# 05_USB_HUB.net
KiCad netlist of a schematic drawn in Altium Designer
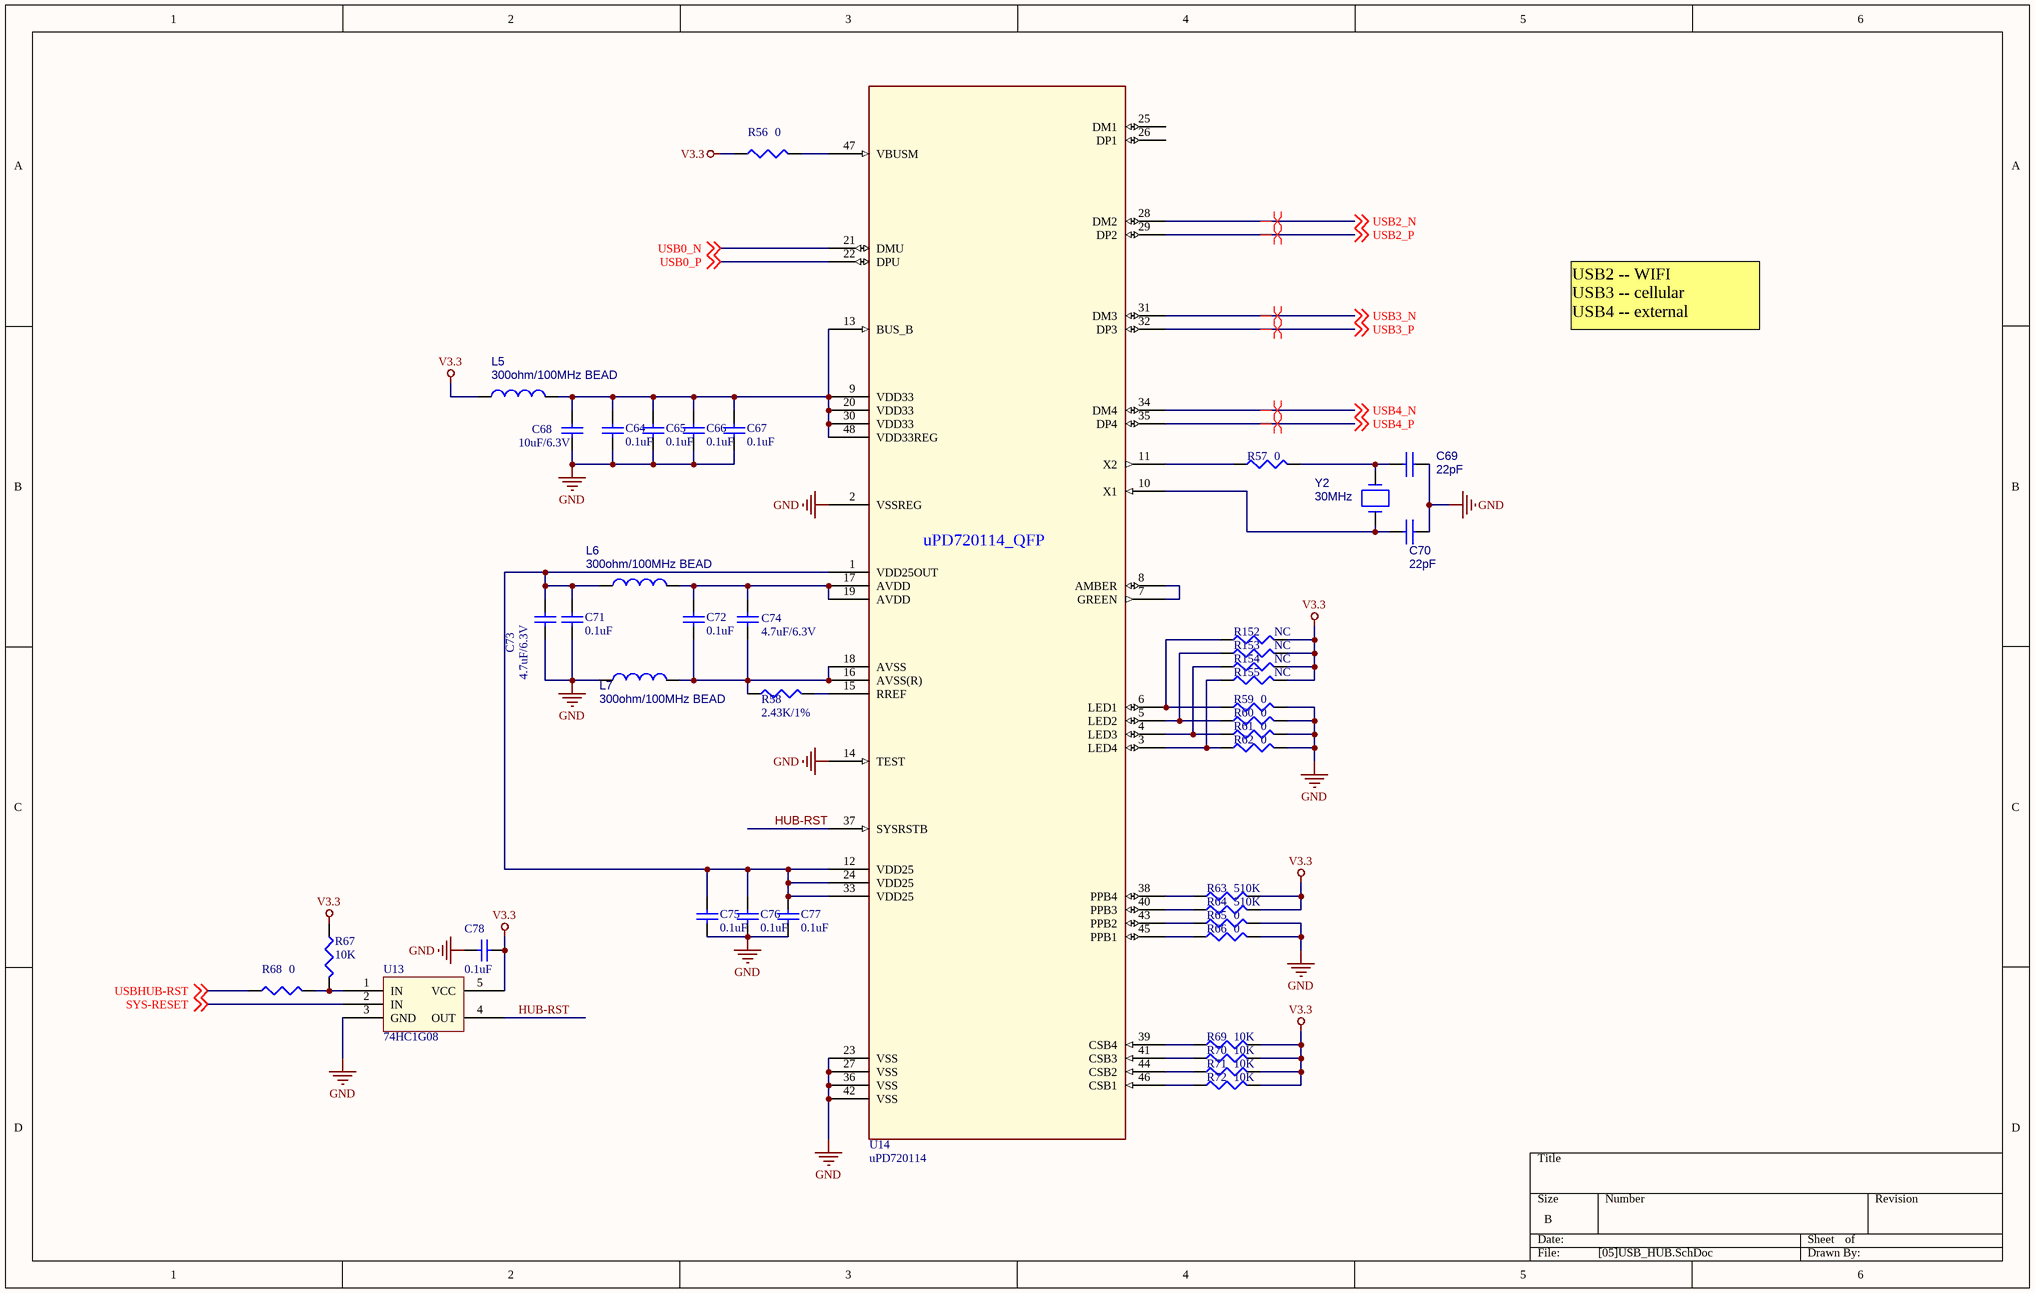
[diagram p0: [05]USB_HUB.SchDoc]

(export (version "E")
  (design (tool "Eeschema 10.0.6"))
  (components
    (comp (ref "C64")
      (value "0.1uF")
      (footprint "0603")
      (description "Capacitor")
      (libsource (lib "Miscellaneous Devices") (part "Cap"))
    )
    (comp (ref "C65")
      (value "0.1uF")
      (footprint "0603")
      (description "Capacitor")
      (libsource (lib "Miscellaneous Devices") (part "Cap"))
    )
    (comp (ref "C66")
      (value "0.1uF")
      (footprint "0603")
      (description "Capacitor")
      (libsource (lib "Miscellaneous Devices") (part "Cap"))
    )
    (comp (ref "C67")
      (value "0.1uF")
      (footprint "0603")
      (description "Capacitor")
      (libsource (lib "Miscellaneous Devices") (part "Cap"))
    )
    (comp (ref "C68")
      (value "10uF/6.3V")
      (footprint "0805")
      (description "Capacitor")
      (libsource (lib "Miscellaneous Devices") (part "Cap"))
    )
    (comp (ref "C69") (value "22pF") (libsource (lib "*") (part "CAP_Dup1")))
    (comp (ref "C70") (value "22pF") (libsource (lib "*") (part "CAP_Dup1")))
    (comp (ref "C71")
      (value "0.1uF")
      (footprint "0603")
      (description "Capacitor")
      (libsource (lib "Miscellaneous Devices") (part "Cap"))
    )
    (comp (ref "C72")
      (value "0.1uF")
      (footprint "0603")
      (description "Capacitor")
      (libsource (lib "Miscellaneous Devices") (part "Cap"))
    )
    (comp (ref "C73")
      (value "4.7uF/6.3V")
      (footprint "0603")
      (description "Capacitor")
      (libsource (lib "Miscellaneous Devices") (part "Cap"))
    )
    (comp (ref "C74")
      (value "4.7uF/6.3V")
      (footprint "0603")
      (description "Capacitor")
      (libsource (lib "Miscellaneous Devices") (part "Cap"))
    )
    (comp (ref "C75")
      (value "0.1uF")
      (footprint "0603")
      (description "Capacitor")
      (libsource (lib "Miscellaneous Devices") (part "Cap"))
    )
    (comp (ref "C76")
      (value "0.1uF")
      (footprint "0603")
      (description "Capacitor")
      (libsource (lib "Miscellaneous Devices") (part "Cap"))
    )
    (comp (ref "C77")
      (value "0.1uF")
      (footprint "0603")
      (description "Capacitor")
      (libsource (lib "Miscellaneous Devices") (part "Cap"))
    )
    (comp (ref "C78")
      (value "0.1uF")
      (footprint "0603")
      (description "Capacitor")
      (libsource (lib "Miscellaneous Devices") (part "Cap"))
    )
    (comp (ref "L5") (value "300ohm/100MHz BEAD") (libsource (lib "*") (part "INDUCTOR_4")))
    (comp (ref "L6") (value "300ohm/100MHz BEAD") (libsource (lib "*") (part "INDUCTOR_4")))
    (comp (ref "L7") (value "300ohm/100MHz BEAD") (libsource (lib "*") (part "INDUCTOR_4")))
    (comp (ref "R56")
      (value "0")
      (footprint "0603")
      (description "Resistor")
      (libsource (lib "Miscellaneous Devices") (part "Res3"))
    )
    (comp (ref "R57")
      (value "0")
      (footprint "0603")
      (description "Resistor")
      (libsource (lib "Miscellaneous Devices") (part "Res3"))
    )
    (comp (ref "R58")
      (value "2.43K/1%")
      (footprint "0603")
      (description "Resistor")
      (libsource (lib "Miscellaneous Devices") (part "Res3"))
    )
    (comp (ref "R59")
      (value "0")
      (footprint "0603")
      (description "Resistor")
      (libsource (lib "Miscellaneous Devices") (part "Res3"))
    )
    (comp (ref "R60")
      (value "0")
      (footprint "0603")
      (description "Resistor")
      (libsource (lib "Miscellaneous Devices") (part "Res3"))
    )
    (comp (ref "R61")
      (value "0")
      (footprint "0603")
      (description "Resistor")
      (libsource (lib "Miscellaneous Devices") (part "Res3"))
    )
    (comp (ref "R62")
      (value "0")
      (footprint "0603")
      (description "Resistor")
      (libsource (lib "Miscellaneous Devices") (part "Res3"))
    )
    (comp (ref "R63")
      (value "510K")
      (footprint "0603")
      (description "Resistor")
      (libsource (lib "Miscellaneous Devices") (part "Res3"))
    )
    (comp (ref "R64")
      (value "510K")
      (footprint "0603")
      (description "Resistor")
      (libsource (lib "Miscellaneous Devices") (part "Res3"))
    )
    (comp (ref "R65")
      (value "0")
      (footprint "0603")
      (description "Resistor")
      (libsource (lib "Miscellaneous Devices") (part "Res3"))
    )
    (comp (ref "R66")
      (value "0")
      (footprint "0603")
      (description "Resistor")
      (libsource (lib "Miscellaneous Devices") (part "Res3"))
    )
    (comp (ref "R67")
      (value "10K")
      (footprint "0603")
      (description "Resistor")
      (libsource (lib "Miscellaneous Devices") (part "Res3"))
    )
    (comp (ref "R68")
      (value "0")
      (footprint "0603")
      (description "Resistor")
      (libsource (lib "Miscellaneous Devices") (part "Res3"))
    )
    (comp (ref "R69")
      (value "10K")
      (footprint "0603")
      (description "Resistor")
      (libsource (lib "Miscellaneous Devices") (part "Res3"))
    )
    (comp (ref "R70")
      (value "10K")
      (footprint "0603")
      (description "Resistor")
      (libsource (lib "Miscellaneous Devices") (part "Res3"))
    )
    (comp (ref "R71")
      (value "10K")
      (footprint "0603")
      (description "Resistor")
      (libsource (lib "Miscellaneous Devices") (part "Res3"))
    )
    (comp (ref "R72")
      (value "10K")
      (footprint "0603")
      (description "Resistor")
      (libsource (lib "Miscellaneous Devices") (part "Res3"))
    )
    (comp (ref "R152")
      (value "NC")
      (footprint "0603")
      (description "Resistor")
      (libsource (lib "Miscellaneous Devices") (part "Res3"))
    )
    (comp (ref "R153")
      (value "NC")
      (footprint "0603")
      (description "Resistor")
      (libsource (lib "Miscellaneous Devices") (part "Res3"))
    )
    (comp (ref "R154")
      (value "NC")
      (footprint "0603")
      (description "Resistor")
      (libsource (lib "Miscellaneous Devices") (part "Res3"))
    )
    (comp (ref "R155")
      (value "NC")
      (footprint "0603")
      (description "Resistor")
      (libsource (lib "Miscellaneous Devices") (part "Res3"))
    )
    (comp (ref "U13") (value "74HC1G08") (footprint "SOT23-5") (libsource (lib "Schlib") (part "74HC1G08")))
    (comp (ref "U14") (value "uPD720114") (footprint "LQFP48") (libsource (lib "*") (part "upd720114_QFP_4")))
    (comp (ref "Y2") (value "30MHz") (libsource (lib "*") (part "CRYSTAL")))
  )
  (nets
    (net (code "1") (name "/HUB-RST") (class "Default")
      (node (ref "U13") (pin "4") (pinfunction "OUT_4") (pintype "passive"))
      (node (ref "U14") (pin "37") (pinfunction "SYSRSTB_37") (pintype "input"))
    )
    (net (code "2") (name "GND") (class "Default")
      (node (ref "C64") (pin "1") (pinfunction "1_1") (pintype "passive"))
      (node (ref "C65") (pin "1") (pinfunction "1_1") (pintype "passive"))
      (node (ref "C66") (pin "1") (pinfunction "1_1") (pintype "passive"))
      (node (ref "C67") (pin "1") (pinfunction "1_1") (pintype "passive"))
      (node (ref "C68") (pin "1") (pinfunction "1_1") (pintype "passive"))
      (node (ref "C69") (pin "1") (pinfunction "1_1") (pintype "passive"))
      (node (ref "C70") (pin "1") (pinfunction "1_1") (pintype "passive"))
      (node (ref "C71") (pin "1") (pinfunction "1_1") (pintype "passive"))
      (node (ref "C73") (pin "1") (pinfunction "1_1") (pintype "passive"))
      (node (ref "C75") (pin "1") (pinfunction "1_1") (pintype "passive"))
      (node (ref "C76") (pin "1") (pinfunction "1_1") (pintype "passive"))
      (node (ref "C77") (pin "1") (pinfunction "1_1") (pintype "passive"))
      (node (ref "C78") (pin "2") (pinfunction "2_2") (pintype "passive"))
      (node (ref "L7") (pin "2") (pinfunction "2_2") (pintype "passive"))
      (node (ref "R59") (pin "2") (pinfunction "2_2") (pintype "passive"))
      (node (ref "R60") (pin "2") (pinfunction "2_2") (pintype "passive"))
      (node (ref "R61") (pin "2") (pinfunction "2_2") (pintype "passive"))
      (node (ref "R62") (pin "2") (pinfunction "2_2") (pintype "passive"))
      (node (ref "R65") (pin "2") (pinfunction "2_2") (pintype "passive"))
      (node (ref "R66") (pin "2") (pinfunction "2_2") (pintype "passive"))
      (node (ref "U13") (pin "3") (pinfunction "GND_3") (pintype "passive"))
      (node (ref "U14") (pin "14") (pinfunction "TEST_14") (pintype "input"))
      (node (ref "U14") (pin "2") (pinfunction "VSSREG_2") (pintype "power_in"))
      (node (ref "U14") (pin "23") (pinfunction "VSS_23") (pintype "power_in"))
      (node (ref "U14") (pin "27") (pinfunction "VSS_27") (pintype "power_in"))
      (node (ref "U14") (pin "36") (pinfunction "VSS_36") (pintype "power_in"))
      (node (ref "U14") (pin "42") (pinfunction "VSS_42") (pintype "power_in"))
    )
    (net (code "3") (name "Net-(C69-Pad2)") (class "Default")
      (node (ref "C69") (pin "2") (pinfunction "2_2") (pintype "passive"))
      (node (ref "R57") (pin "2") (pinfunction "2_2") (pintype "passive"))
      (node (ref "Y2") (pin "2") (pinfunction "2_2") (pintype "passive"))
    )
    (net (code "4") (name "Net-(C72-Pad2)") (class "Default")
      (node (ref "C72") (pin "2") (pinfunction "2_2") (pintype "passive"))
      (node (ref "C74") (pin "2") (pinfunction "2_2") (pintype "passive"))
      (node (ref "L6") (pin "1") (pinfunction "1_1") (pintype "passive"))
      (node (ref "U14") (pin "17") (pinfunction "AVDD_17") (pintype "power_in"))
      (node (ref "U14") (pin "19") (pinfunction "AVDD_19") (pintype "power_in"))
    )
    (net (code "5") (name "Net-(R67-Pad2)") (class "Default")
      (node (ref "R67") (pin "2") (pinfunction "2_2") (pintype "passive"))
      (node (ref "R68") (pin "2") (pinfunction "2_2") (pintype "passive"))
      (node (ref "U13") (pin "1") (pinfunction "IN_1") (pintype "passive"))
    )
    (net (code "6") (name "Net-(U14-AMBER)") (class "Default")
      (node (ref "U14") (pin "7") (pinfunction "GREEN_7") (pintype "output"))
      (node (ref "U14") (pin "8") (pinfunction "AMBER_8") (pintype "bidirectional"))
    )
    (net (code "7") (name "Net-(U14-AVSS(R))") (class "Default")
      (node (ref "C72") (pin "1") (pinfunction "1_1") (pintype "passive"))
      (node (ref "C74") (pin "1") (pinfunction "1_1") (pintype "passive"))
      (node (ref "L7") (pin "1") (pinfunction "1_1") (pintype "passive"))
      (node (ref "R58") (pin "1") (pinfunction "1_1") (pintype "passive"))
      (node (ref "U14") (pin "16") (pinfunction "AVSS(R)_16") (pintype "power_in"))
      (node (ref "U14") (pin "18") (pinfunction "AVSS_18") (pintype "power_in"))
    )
    (net (code "8") (name "Net-(U14-BUS_B)") (class "Default")
      (node (ref "C64") (pin "2") (pinfunction "2_2") (pintype "passive"))
      (node (ref "C65") (pin "2") (pinfunction "2_2") (pintype "passive"))
      (node (ref "C66") (pin "2") (pinfunction "2_2") (pintype "passive"))
      (node (ref "C67") (pin "2") (pinfunction "2_2") (pintype "passive"))
      (node (ref "C68") (pin "2") (pinfunction "2_2") (pintype "passive"))
      (node (ref "L5") (pin "1") (pinfunction "1_1") (pintype "passive"))
      (node (ref "U14") (pin "13") (pinfunction "BUS_B_13") (pintype "input"))
      (node (ref "U14") (pin "20") (pinfunction "VDD33_20") (pintype "power_in"))
      (node (ref "U14") (pin "30") (pinfunction "VDD33_30") (pintype "power_in"))
      (node (ref "U14") (pin "48") (pinfunction "VDD33REG_48") (pintype "power_in"))
      (node (ref "U14") (pin "9") (pinfunction "VDD33_9") (pintype "power_in"))
    )
    (net (code "9") (name "Net-(U14-CSB1)") (class "Default")
      (node (ref "R72") (pin "1") (pinfunction "1_1") (pintype "passive"))
      (node (ref "U14") (pin "46") (pinfunction "CSB1_46") (pintype "input"))
    )
    (net (code "10") (name "Net-(U14-CSB2)") (class "Default")
      (node (ref "R71") (pin "1") (pinfunction "1_1") (pintype "passive"))
      (node (ref "U14") (pin "44") (pinfunction "CSB2_44") (pintype "input"))
    )
    (net (code "11") (name "Net-(U14-CSB3)") (class "Default")
      (node (ref "R70") (pin "1") (pinfunction "1_1") (pintype "passive"))
      (node (ref "U14") (pin "41") (pinfunction "CSB3_41") (pintype "input"))
    )
    (net (code "12") (name "Net-(U14-CSB4)") (class "Default")
      (node (ref "R69") (pin "1") (pinfunction "1_1") (pintype "passive"))
      (node (ref "U14") (pin "39") (pinfunction "CSB4_39") (pintype "input"))
    )
    (net (code "13") (name "Net-(U14-LED1)") (class "Default")
      (node (ref "R152") (pin "1") (pinfunction "1_1") (pintype "passive"))
      (node (ref "R59") (pin "1") (pinfunction "1_1") (pintype "passive"))
      (node (ref "U14") (pin "6") (pinfunction "LED1_6") (pintype "bidirectional"))
    )
    (net (code "14") (name "Net-(U14-LED2)") (class "Default")
      (node (ref "R153") (pin "1") (pinfunction "1_1") (pintype "passive"))
      (node (ref "R60") (pin "1") (pinfunction "1_1") (pintype "passive"))
      (node (ref "U14") (pin "5") (pinfunction "LED2_5") (pintype "bidirectional"))
    )
    (net (code "15") (name "Net-(U14-LED3)") (class "Default")
      (node (ref "R154") (pin "1") (pinfunction "1_1") (pintype "passive"))
      (node (ref "R61") (pin "1") (pinfunction "1_1") (pintype "passive"))
      (node (ref "U14") (pin "4") (pinfunction "LED3_4") (pintype "bidirectional"))
    )
    (net (code "16") (name "Net-(U14-LED4)") (class "Default")
      (node (ref "R155") (pin "1") (pinfunction "1_1") (pintype "passive"))
      (node (ref "R62") (pin "1") (pinfunction "1_1") (pintype "passive"))
      (node (ref "U14") (pin "3") (pinfunction "LED4_3") (pintype "bidirectional"))
    )
    (net (code "17") (name "Net-(U14-PPB1)") (class "Default")
      (node (ref "R66") (pin "1") (pinfunction "1_1") (pintype "passive"))
      (node (ref "U14") (pin "45") (pinfunction "PPB1_45") (pintype "bidirectional"))
    )
    (net (code "18") (name "Net-(U14-PPB2)") (class "Default")
      (node (ref "R65") (pin "1") (pinfunction "1_1") (pintype "passive"))
      (node (ref "U14") (pin "43") (pinfunction "PPB2_43") (pintype "bidirectional"))
    )
    (net (code "19") (name "Net-(U14-PPB3)") (class "Default")
      (node (ref "R64") (pin "1") (pinfunction "1_1") (pintype "passive"))
      (node (ref "U14") (pin "40") (pinfunction "PPB3_40") (pintype "bidirectional"))
    )
    (net (code "20") (name "Net-(U14-PPB4)") (class "Default")
      (node (ref "R63") (pin "1") (pinfunction "1_1") (pintype "passive"))
      (node (ref "U14") (pin "38") (pinfunction "PPB4_38") (pintype "bidirectional"))
    )
    (net (code "21") (name "Net-(U14-RREF)") (class "Default")
      (node (ref "R58") (pin "2") (pinfunction "2_2") (pintype "passive"))
      (node (ref "U14") (pin "15") (pinfunction "RREF_15") (pintype "passive"))
    )
    (net (code "22") (name "Net-(U14-VBUSM)") (class "Default")
      (node (ref "R56") (pin "2") (pinfunction "2_2") (pintype "passive"))
      (node (ref "U14") (pin "47") (pinfunction "VBUSM_47") (pintype "input"))
    )
    (net (code "23") (name "Net-(U14-VDD25OUT)") (class "Default")
      (node (ref "C71") (pin "2") (pinfunction "2_2") (pintype "passive"))
      (node (ref "C73") (pin "2") (pinfunction "2_2") (pintype "passive"))
      (node (ref "C75") (pin "2") (pinfunction "2_2") (pintype "passive"))
      (node (ref "C76") (pin "2") (pinfunction "2_2") (pintype "passive"))
      (node (ref "C77") (pin "2") (pinfunction "2_2") (pintype "passive"))
      (node (ref "L6") (pin "2") (pinfunction "2_2") (pintype "passive"))
      (node (ref "U14") (pin "1") (pinfunction "VDD25OUT_1") (pintype "power_in"))
      (node (ref "U14") (pin "12") (pinfunction "VDD25_12") (pintype "power_in"))
      (node (ref "U14") (pin "24") (pinfunction "VDD25_24") (pintype "power_in"))
      (node (ref "U14") (pin "33") (pinfunction "VDD25_33") (pintype "power_in"))
    )
    (net (code "24") (name "Net-(U14-X1)") (class "Default")
      (node (ref "C70") (pin "2") (pinfunction "2_2") (pintype "passive"))
      (node (ref "U14") (pin "10") (pinfunction "X1_10") (pintype "input"))
      (node (ref "Y2") (pin "1") (pinfunction "1_1") (pintype "passive"))
    )
    (net (code "25") (name "Net-(U14-X2)") (class "Default")
      (node (ref "R57") (pin "1") (pinfunction "1_1") (pintype "passive"))
      (node (ref "U14") (pin "11") (pinfunction "X2_11") (pintype "output"))
    )
    (net (code "26") (name "SYS-RESET") (class "Default")
      (node (ref "U13") (pin "2") (pinfunction "IN_2") (pintype "passive"))
    )
    (net (code "27") (name "USB0_N") (class "Default")
      (node (ref "U14") (pin "21") (pinfunction "DMU_21") (pintype "bidirectional"))
    )
    (net (code "28") (name "USB0_P") (class "Default")
      (node (ref "U14") (pin "22") (pinfunction "DPU_22") (pintype "bidirectional"))
    )
    (net (code "29") (name "USB2_N") (class "Default")
      (node (ref "U14") (pin "28") (pinfunction "DM2_28") (pintype "bidirectional"))
    )
    (net (code "30") (name "USB2_P") (class "Default")
      (node (ref "U14") (pin "29") (pinfunction "DP2_29") (pintype "bidirectional"))
    )
    (net (code "31") (name "USB3_N") (class "Default")
      (node (ref "U14") (pin "31") (pinfunction "DM3_31") (pintype "bidirectional"))
    )
    (net (code "32") (name "USB3_P") (class "Default")
      (node (ref "U14") (pin "32") (pinfunction "DP3_32") (pintype "bidirectional"))
    )
    (net (code "33") (name "USB4_N") (class "Default")
      (node (ref "U14") (pin "34") (pinfunction "DM4_34") (pintype "bidirectional"))
    )
    (net (code "34") (name "USB4_P") (class "Default")
      (node (ref "U14") (pin "35") (pinfunction "DP4_35") (pintype "bidirectional"))
    )
    (net (code "35") (name "USBHUB-RST") (class "Default")
      (node (ref "R68") (pin "1") (pinfunction "1_1") (pintype "passive"))
    )
    (net (code "36") (name "V3.3") (class "Default")
      (node (ref "C78") (pin "1") (pinfunction "1_1") (pintype "passive"))
      (node (ref "L5") (pin "2") (pinfunction "2_2") (pintype "passive"))
      (node (ref "R152") (pin "2") (pinfunction "2_2") (pintype "passive"))
      (node (ref "R153") (pin "2") (pinfunction "2_2") (pintype "passive"))
      (node (ref "R154") (pin "2") (pinfunction "2_2") (pintype "passive"))
      (node (ref "R155") (pin "2") (pinfunction "2_2") (pintype "passive"))
      (node (ref "R56") (pin "1") (pinfunction "1_1") (pintype "passive"))
      (node (ref "R63") (pin "2") (pinfunction "2_2") (pintype "passive"))
      (node (ref "R64") (pin "2") (pinfunction "2_2") (pintype "passive"))
      (node (ref "R67") (pin "1") (pinfunction "1_1") (pintype "passive"))
      (node (ref "R69") (pin "2") (pinfunction "2_2") (pintype "passive"))
      (node (ref "R70") (pin "2") (pinfunction "2_2") (pintype "passive"))
      (node (ref "R71") (pin "2") (pinfunction "2_2") (pintype "passive"))
      (node (ref "R72") (pin "2") (pinfunction "2_2") (pintype "passive"))
      (node (ref "U13") (pin "5") (pinfunction "VCC_5") (pintype "passive"))
    )
    (net (code "37") (name "unconnected-(U14-DM1-Pad25)") (class "Default")
      (node (ref "U14") (pin "25") (pinfunction "DM1_25") (pintype "bidirectional"))
    )
    (net (code "38") (name "unconnected-(U14-DP1-Pad26)") (class "Default")
      (node (ref "U14") (pin "26") (pinfunction "DP1_26") (pintype "bidirectional"))
    )
  )
)
